# 9_-CAMERA_POWER_CONTROLLER.net
KiCad netlist of a schematic drawn in Altium Designer
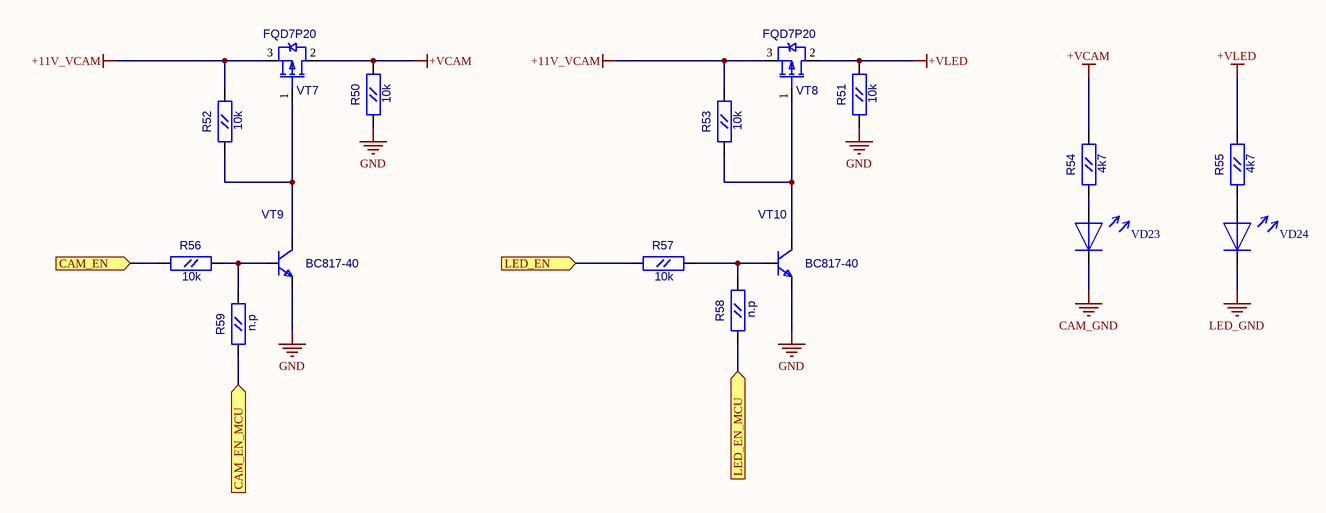
[diagram p0: [9]-CAMERA_POWER_CONTROLLER.SchDoc]

(export (version "E")
  (design (tool "Eeschema 10.0.6"))
  (components
    (comp (ref "R50")
      (value "10k")
      (footprint "RC0603")
      (description "RC0603")
      (libsource (lib "fizik_lib") (part "RC0603"))
    )
    (comp (ref "R51")
      (value "10k")
      (footprint "RC0603")
      (description "RC0603")
      (libsource (lib "fizik_lib") (part "RC0603"))
    )
    (comp (ref "R52")
      (value "10k")
      (footprint "RC0603")
      (description "RC0603")
      (libsource (lib "fizik_lib") (part "RC0603"))
    )
    (comp (ref "R53")
      (value "10k")
      (footprint "RC0603")
      (description "RC0603")
      (libsource (lib "fizik_lib") (part "RC0603"))
    )
    (comp (ref "R54")
      (value "4k7")
      (footprint "RC0603")
      (description "RC0603")
      (libsource (lib "gprs_modem_2") (part "RC0603"))
    )
    (comp (ref "R55")
      (value "4k7")
      (footprint "RC0603")
      (description "RC0603")
      (libsource (lib "gprs_modem_2") (part "RC0603"))
    )
    (comp (ref "R56")
      (value "10k")
      (footprint "RC0603")
      (description "RC0603")
      (libsource (lib "fizik_lib") (part "RC0603"))
    )
    (comp (ref "R57")
      (value "10k")
      (footprint "RC0603")
      (description "RC0603")
      (libsource (lib "fizik_lib") (part "RC0603"))
    )
    (comp (ref "R58")
      (value "n.p")
      (footprint "RC0603")
      (description "RC0603")
      (libsource (lib "fizik_lib") (part "RC0603"))
    )
    (comp (ref "R59")
      (value "n.p")
      (footprint "RC0603")
      (description "RC0603")
      (libsource (lib "fizik_lib") (part "RC0603"))
    )
    (comp (ref "VD23")
      (value "LED_0805")
      (footprint "LED0805")
      (libsource (lib "gprs_modem_2") (part "LED_0805"))
    )
    (comp (ref "VD24")
      (value "LED_0805")
      (footprint "LED0805")
      (libsource (lib "gprs_modem_2") (part "LED_0805"))
    )
    (comp (ref "VT7")
      (value "FQD7P20")
      (footprint "D-PAK(TO-252AA)")
      (description "HEXFET Power MOSFET")
      (libsource (lib "gprs_modem_2") (part "IRFR9220"))
    )
    (comp (ref "VT8")
      (value "FQD7P20")
      (footprint "D-PAK(TO-252AA)")
      (description "HEXFET Power MOSFET")
      (libsource (lib "gprs_modem_2") (part "IRFR9220"))
    )
    (comp (ref "VT9")
      (value "BC817-40")
      (footprint "SOT-23(123)")
      (description "NPN 500ma transistor")
      (libsource (lib "fizik_lib") (part "BC846BLT1"))
    )
    (comp (ref "VT10")
      (value "BC817-40")
      (footprint "SOT-23(123)")
      (description "NPN 500ma transistor")
      (libsource (lib "fizik_lib") (part "BC846BLT1"))
    )
  )
  (nets
    (net (code "1") (name "+11V_VCAM") (class "Default")
      (node (ref "R52") (pin "2") (pinfunction "B_2") (pintype "passive"))
      (node (ref "R53") (pin "2") (pinfunction "B_2") (pintype "passive"))
      (node (ref "VT7") (pin "3") (pinfunction "S_3") (pintype "passive"))
      (node (ref "VT8") (pin "3") (pinfunction "S_3") (pintype "passive"))
    )
    (net (code "2") (name "+VCAM") (class "Default")
      (node (ref "R50") (pin "2") (pinfunction "B_2") (pintype "passive"))
      (node (ref "R54") (pin "2") (pinfunction "B_2") (pintype "passive"))
      (node (ref "VT7") (pin "2") (pinfunction "D_2") (pintype "passive"))
    )
    (net (code "3") (name "+VLED") (class "Default")
      (node (ref "R51") (pin "2") (pinfunction "B_2") (pintype "passive"))
      (node (ref "R55") (pin "2") (pinfunction "B_2") (pintype "passive"))
      (node (ref "VT8") (pin "2") (pinfunction "D_2") (pintype "passive"))
    )
    (net (code "4") (name "/CAM_EN") (class "Default")
      (node (ref "R56") (pin "1") (pinfunction "A_1") (pintype "passive"))
    )
    (net (code "5") (name "/CAM_EN_MCU") (class "Default")
      (node (ref "R59") (pin "1") (pinfunction "A_1") (pintype "passive"))
    )
    (net (code "6") (name "/LED_EN") (class "Default")
      (node (ref "R57") (pin "1") (pinfunction "A_1") (pintype "passive"))
    )
    (net (code "7") (name "/LED_EN_MCU") (class "Default")
      (node (ref "R58") (pin "1") (pinfunction "A_1") (pintype "passive"))
    )
    (net (code "8") (name "CAM_GND") (class "Default") (node (ref "VD23") (pin "2") (pintype "passive")))
    (net (code "9") (name "GND") (class "Default")
      (node (ref "R50") (pin "1") (pinfunction "A_1") (pintype "passive"))
      (node (ref "R51") (pin "1") (pinfunction "A_1") (pintype "passive"))
      (node (ref "VT10") (pin "2") (pinfunction "E_2") (pintype "passive"))
      (node (ref "VT9") (pin "2") (pinfunction "E_2") (pintype "passive"))
    )
    (net (code "10") (name "LED_GND") (class "Default") (node (ref "VD24") (pin "2") (pintype "passive")))
    (net (code "11") (name "Net-(R52-A)") (class "Default")
      (node (ref "R52") (pin "1") (pinfunction "A_1") (pintype "passive"))
      (node (ref "VT7") (pin "1") (pinfunction "G_1") (pintype "passive"))
      (node (ref "VT9") (pin "3") (pinfunction "C_3") (pintype "passive"))
    )
    (net (code "12") (name "Net-(R53-A)") (class "Default")
      (node (ref "R53") (pin "1") (pinfunction "A_1") (pintype "passive"))
      (node (ref "VT10") (pin "3") (pinfunction "C_3") (pintype "passive"))
      (node (ref "VT8") (pin "1") (pinfunction "G_1") (pintype "passive"))
    )
    (net (code "13") (name "Net-(R54-A)") (class "Default")
      (node (ref "R54") (pin "1") (pinfunction "A_1") (pintype "passive"))
      (node (ref "VD23") (pin "1") (pintype "passive"))
    )
    (net (code "14") (name "Net-(R55-A)") (class "Default")
      (node (ref "R55") (pin "1") (pinfunction "A_1") (pintype "passive"))
      (node (ref "VD24") (pin "1") (pintype "passive"))
    )
    (net (code "15") (name "Net-(R56-B)") (class "Default")
      (node (ref "R56") (pin "2") (pinfunction "B_2") (pintype "passive"))
      (node (ref "R59") (pin "2") (pinfunction "B_2") (pintype "passive"))
      (node (ref "VT9") (pin "1") (pinfunction "B_1") (pintype "passive"))
    )
    (net (code "16") (name "Net-(R57-B)") (class "Default")
      (node (ref "R57") (pin "2") (pinfunction "B_2") (pintype "passive"))
      (node (ref "R58") (pin "2") (pinfunction "B_2") (pintype "passive"))
      (node (ref "VT10") (pin "1") (pinfunction "B_1") (pintype "passive"))
    )
  )
)
